# Skema_Gate_Logic.net
KiCad netlist of a schematic drawn in Altium Designer
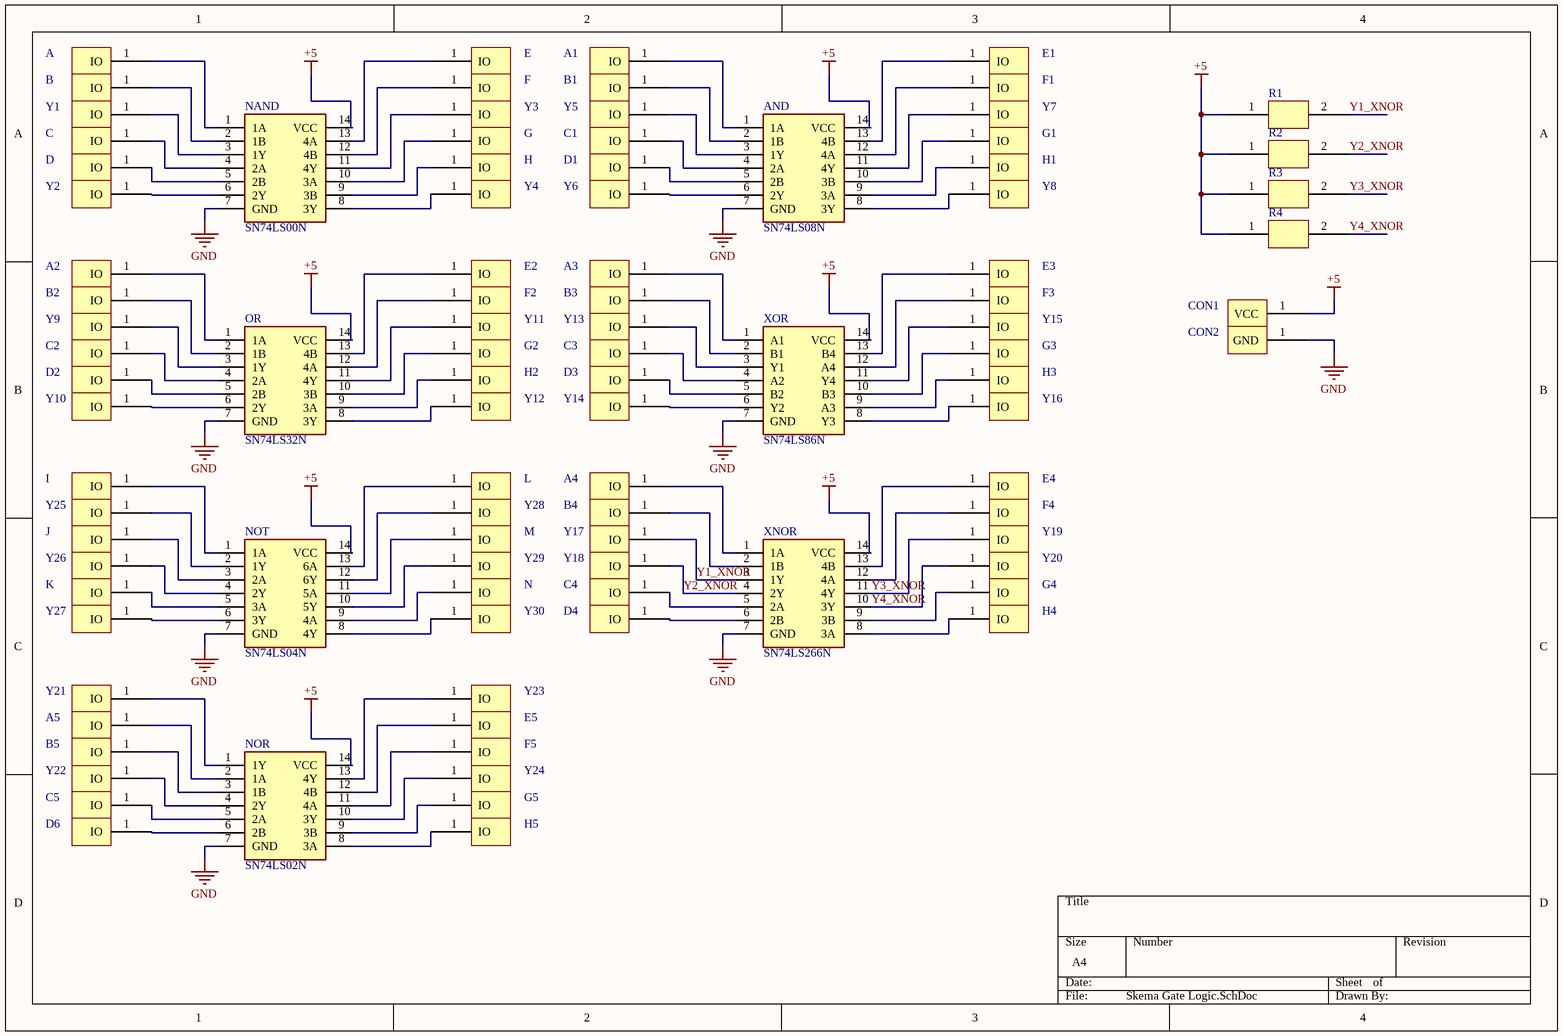
[diagram p0: Skema Gate Logic.SchDoc]

(export (version "E")
  (design (tool "Eeschema 10.0.6"))
  (components
    (comp (ref "A")
      (value "Female_Connector_Banana")
      (footprint "F_Banana")
      (libsource (lib "") (part "Female_Connector_Banana_1"))
    )
    (comp (ref "A1")
      (value "Female_Connector_Banana")
      (footprint "F_Banana")
      (libsource (lib "") (part "Female_Connector_Banana_1"))
    )
    (comp (ref "A2")
      (value "Female_Connector_Banana")
      (footprint "F_Banana")
      (libsource (lib "") (part "Female_Connector_Banana_1"))
    )
    (comp (ref "A3")
      (value "Female_Connector_Banana")
      (footprint "F_Banana")
      (libsource (lib "") (part "Female_Connector_Banana_1"))
    )
    (comp (ref "A4")
      (value "Female_Connector_Banana")
      (footprint "F_Banana")
      (libsource (lib "") (part "Female_Connector_Banana_1"))
    )
    (comp (ref "A5")
      (value "Female_Connector_Banana")
      (footprint "F_Banana")
      (libsource (lib "") (part "Female_Connector_Banana_1"))
    )
    (comp (ref "AND")
      (value "SN74LS08N")
      (footprint "SamacSys:DIP794W53P254L1930H508Q14N")
      (description "Integrated Circuit")
      (fields (field (name "MOUSER PART NUMBER") "595-SN74LS08N"))
      (libsource (lib "SamacSys") (part "SN74LS08N"))
    )
    (comp (ref "B")
      (value "Female_Connector_Banana")
      (footprint "F_Banana")
      (libsource (lib "") (part "Female_Connector_Banana_1"))
    )
    (comp (ref "B1")
      (value "Female_Connector_Banana")
      (footprint "F_Banana")
      (libsource (lib "") (part "Female_Connector_Banana_1"))
    )
    (comp (ref "B2")
      (value "Female_Connector_Banana")
      (footprint "F_Banana")
      (libsource (lib "") (part "Female_Connector_Banana_1"))
    )
    (comp (ref "B3")
      (value "Female_Connector_Banana")
      (footprint "F_Banana")
      (libsource (lib "") (part "Female_Connector_Banana_1"))
    )
    (comp (ref "B4")
      (value "Female_Connector_Banana")
      (footprint "F_Banana")
      (libsource (lib "") (part "Female_Connector_Banana_1"))
    )
    (comp (ref "B5")
      (value "Female_Connector_Banana")
      (footprint "F_Banana")
      (libsource (lib "") (part "Female_Connector_Banana_1"))
    )
    (comp (ref "C")
      (value "Female_Connector_Banana")
      (footprint "F_Banana")
      (libsource (lib "") (part "Female_Connector_Banana_1"))
    )
    (comp (ref "C1")
      (value "Female_Connector_Banana")
      (footprint "F_Banana")
      (libsource (lib "") (part "Female_Connector_Banana_1"))
    )
    (comp (ref "C2")
      (value "Female_Connector_Banana")
      (footprint "F_Banana")
      (libsource (lib "") (part "Female_Connector_Banana_1"))
    )
    (comp (ref "C3")
      (value "Female_Connector_Banana")
      (footprint "F_Banana")
      (libsource (lib "") (part "Female_Connector_Banana_1"))
    )
    (comp (ref "C4")
      (value "Female_Connector_Banana")
      (footprint "F_Banana")
      (libsource (lib "") (part "Female_Connector_Banana_1"))
    )
    (comp (ref "C5")
      (value "Female_Connector_Banana")
      (footprint "F_Banana")
      (libsource (lib "") (part "Female_Connector_Banana_1"))
    )
    (comp (ref "CON1")
      (value "Female_Connector_Banana")
      (footprint "F_Banana")
      (libsource (lib "") (part "Female_Connector_Banana_3"))
    )
    (comp (ref "CON2")
      (value "Female_Connector_Banana")
      (footprint "F_Banana")
      (libsource (lib "") (part "Female_Connector_Banana_2"))
    )
    (comp (ref "D")
      (value "Female_Connector_Banana")
      (footprint "F_Banana")
      (libsource (lib "") (part "Female_Connector_Banana_1"))
    )
    (comp (ref "D1")
      (value "Female_Connector_Banana")
      (footprint "F_Banana")
      (libsource (lib "") (part "Female_Connector_Banana_1"))
    )
    (comp (ref "D2")
      (value "Female_Connector_Banana")
      (footprint "F_Banana")
      (libsource (lib "") (part "Female_Connector_Banana_1"))
    )
    (comp (ref "D3")
      (value "Female_Connector_Banana")
      (footprint "F_Banana")
      (libsource (lib "") (part "Female_Connector_Banana_1"))
    )
    (comp (ref "D4")
      (value "Female_Connector_Banana")
      (footprint "F_Banana")
      (libsource (lib "") (part "Female_Connector_Banana_1"))
    )
    (comp (ref "D6")
      (value "Female_Connector_Banana")
      (footprint "F_Banana")
      (libsource (lib "") (part "Female_Connector_Banana_1"))
    )
    (comp (ref "E")
      (value "Female_Connector_Banana")
      (footprint "F_Banana")
      (libsource (lib "SamacSys") (part "Female_Connector_Banana"))
    )
    (comp (ref "E1")
      (value "Female_Connector_Banana")
      (footprint "F_Banana")
      (libsource (lib "SamacSys") (part "Female_Connector_Banana"))
    )
    (comp (ref "E2")
      (value "Female_Connector_Banana")
      (footprint "F_Banana")
      (libsource (lib "SamacSys") (part "Female_Connector_Banana"))
    )
    (comp (ref "E3")
      (value "Female_Connector_Banana")
      (footprint "F_Banana")
      (libsource (lib "SamacSys") (part "Female_Connector_Banana"))
    )
    (comp (ref "E4")
      (value "Female_Connector_Banana")
      (footprint "F_Banana")
      (libsource (lib "SamacSys") (part "Female_Connector_Banana"))
    )
    (comp (ref "E5")
      (value "Female_Connector_Banana")
      (footprint "F_Banana")
      (libsource (lib "SamacSys") (part "Female_Connector_Banana"))
    )
    (comp (ref "F")
      (value "Female_Connector_Banana")
      (footprint "F_Banana")
      (libsource (lib "SamacSys") (part "Female_Connector_Banana"))
    )
    (comp (ref "F1")
      (value "Female_Connector_Banana")
      (footprint "F_Banana")
      (libsource (lib "SamacSys") (part "Female_Connector_Banana"))
    )
    (comp (ref "F2")
      (value "Female_Connector_Banana")
      (footprint "F_Banana")
      (libsource (lib "SamacSys") (part "Female_Connector_Banana"))
    )
    (comp (ref "F3")
      (value "Female_Connector_Banana")
      (footprint "F_Banana")
      (libsource (lib "SamacSys") (part "Female_Connector_Banana"))
    )
    (comp (ref "F4")
      (value "Female_Connector_Banana")
      (footprint "F_Banana")
      (libsource (lib "SamacSys") (part "Female_Connector_Banana"))
    )
    (comp (ref "F5")
      (value "Female_Connector_Banana")
      (footprint "F_Banana")
      (libsource (lib "SamacSys") (part "Female_Connector_Banana"))
    )
    (comp (ref "G")
      (value "Female_Connector_Banana")
      (footprint "F_Banana")
      (libsource (lib "SamacSys") (part "Female_Connector_Banana"))
    )
    (comp (ref "G1")
      (value "Female_Connector_Banana")
      (footprint "F_Banana")
      (libsource (lib "SamacSys") (part "Female_Connector_Banana"))
    )
    (comp (ref "G2")
      (value "Female_Connector_Banana")
      (footprint "F_Banana")
      (libsource (lib "SamacSys") (part "Female_Connector_Banana"))
    )
    (comp (ref "G3")
      (value "Female_Connector_Banana")
      (footprint "F_Banana")
      (libsource (lib "SamacSys") (part "Female_Connector_Banana"))
    )
    (comp (ref "G4")
      (value "Female_Connector_Banana")
      (footprint "F_Banana")
      (libsource (lib "SamacSys") (part "Female_Connector_Banana"))
    )
    (comp (ref "G5")
      (value "Female_Connector_Banana")
      (footprint "F_Banana")
      (libsource (lib "SamacSys") (part "Female_Connector_Banana"))
    )
    (comp (ref "H")
      (value "Female_Connector_Banana")
      (footprint "F_Banana")
      (libsource (lib "SamacSys") (part "Female_Connector_Banana"))
    )
    (comp (ref "H1")
      (value "Female_Connector_Banana")
      (footprint "F_Banana")
      (libsource (lib "SamacSys") (part "Female_Connector_Banana"))
    )
    (comp (ref "H2")
      (value "Female_Connector_Banana")
      (footprint "F_Banana")
      (libsource (lib "SamacSys") (part "Female_Connector_Banana"))
    )
    (comp (ref "H3")
      (value "Female_Connector_Banana")
      (footprint "F_Banana")
      (libsource (lib "SamacSys") (part "Female_Connector_Banana"))
    )
    (comp (ref "H4")
      (value "Female_Connector_Banana")
      (footprint "F_Banana")
      (libsource (lib "SamacSys") (part "Female_Connector_Banana"))
    )
    (comp (ref "H5")
      (value "Female_Connector_Banana")
      (footprint "F_Banana")
      (libsource (lib "SamacSys") (part "Female_Connector_Banana"))
    )
    (comp (ref "I")
      (value "Female_Connector_Banana")
      (footprint "F_Banana")
      (libsource (lib "") (part "Female_Connector_Banana_1"))
    )
    (comp (ref "J")
      (value "Female_Connector_Banana")
      (footprint "F_Banana")
      (libsource (lib "") (part "Female_Connector_Banana_1"))
    )
    (comp (ref "K")
      (value "Female_Connector_Banana")
      (footprint "F_Banana")
      (libsource (lib "") (part "Female_Connector_Banana_1"))
    )
    (comp (ref "L")
      (value "Female_Connector_Banana")
      (footprint "F_Banana")
      (libsource (lib "SamacSys") (part "Female_Connector_Banana"))
    )
    (comp (ref "M")
      (value "Female_Connector_Banana")
      (footprint "F_Banana")
      (libsource (lib "SamacSys") (part "Female_Connector_Banana"))
    )
    (comp (ref "N")
      (value "Female_Connector_Banana")
      (footprint "F_Banana")
      (libsource (lib "SamacSys") (part "Female_Connector_Banana"))
    )
    (comp (ref "NAND")
      (value "SN74LS00N")
      (footprint "SamacSys:DIP794W53P254L1930H508Q14N")
      (description "Integrated Circuit")
      (fields (field (name "MOUSER PART NUMBER") "595-SN74LS00N"))
      (libsource (lib "SamacSys") (part "SN74LS00N"))
    )
    (comp (ref "NOR")
      (value "SN74LS02N")
      (footprint "SamacSys:DIP794W53P254L1930H508Q14N")
      (description "Integrated Circuit")
      (fields (field (name "MOUSER PART NUMBER") "595-SN74LS02N"))
      (libsource (lib "SamacSys") (part "SN74LS02N"))
    )
    (comp (ref "NOT")
      (value "SN74LS04N")
      (footprint "SamacSys:DIP794W53P254L1930H508Q14N")
      (description "Integrated Circuit")
      (fields (field (name "MOUSER PART NUMBER") "595-SN74LS04N"))
      (libsource (lib "SamacSys") (part "SN74LS04N"))
    )
    (comp (ref "OR")
      (value "SN74LS32N")
      (footprint "SamacSys:DIP794W53P254L1930H508Q14N")
      (description "Integrated Circuit")
      (fields (field (name "MOUSER PART NUMBER") "595-SN74LS32N"))
      (libsource (lib "SamacSys") (part "SN74LS32N"))
    )
    (comp (ref "R1")
      (value "Resistor")
      (footprint "Resistor")
      (description "Fixed Resistance")
      (libsource (lib "Header") (part "Resistor"))
    )
    (comp (ref "R2")
      (value "Resistor")
      (footprint "Resistor")
      (description "Fixed Resistance")
      (libsource (lib "Header") (part "Resistor"))
    )
    (comp (ref "R3")
      (value "Resistor")
      (footprint "Resistor")
      (description "Fixed Resistance")
      (libsource (lib "Header") (part "Resistor"))
    )
    (comp (ref "R4")
      (value "Resistor")
      (footprint "Resistor")
      (description "Fixed Resistance")
      (libsource (lib "Header") (part "Resistor"))
    )
    (comp (ref "XNOR")
      (value "SN74LS266N")
      (footprint "SamacSys:DIP794W53P254L1930H508Q14N")
      (description "Integrated Circuit")
      (fields (field (name "MOUSER PART NUMBER") "595-SN74LS266N"))
      (libsource (lib "SamacSys") (part "SN74LS266N"))
    )
    (comp (ref "XOR")
      (value "SN74LS86N")
      (footprint "SamacSys:DIP794W53P254L1930H508Q14N")
      (description "Integrated Circuit")
      (libsource (lib "SamacSys") (part "SN74LS86N"))
    )
    (comp (ref "Y1")
      (value "Female_Connector_Banana")
      (footprint "F_Banana")
      (libsource (lib "") (part "Female_Connector_Banana_1"))
    )
    (comp (ref "Y2")
      (value "Female_Connector_Banana")
      (footprint "F_Banana")
      (libsource (lib "") (part "Female_Connector_Banana_1"))
    )
    (comp (ref "Y3")
      (value "Female_Connector_Banana")
      (footprint "F_Banana")
      (libsource (lib "SamacSys") (part "Female_Connector_Banana"))
    )
    (comp (ref "Y4")
      (value "Female_Connector_Banana")
      (footprint "F_Banana")
      (libsource (lib "SamacSys") (part "Female_Connector_Banana"))
    )
    (comp (ref "Y5")
      (value "Female_Connector_Banana")
      (footprint "F_Banana")
      (libsource (lib "") (part "Female_Connector_Banana_1"))
    )
    (comp (ref "Y6")
      (value "Female_Connector_Banana")
      (footprint "F_Banana")
      (libsource (lib "") (part "Female_Connector_Banana_1"))
    )
    (comp (ref "Y7")
      (value "Female_Connector_Banana")
      (footprint "F_Banana")
      (libsource (lib "SamacSys") (part "Female_Connector_Banana"))
    )
    (comp (ref "Y8")
      (value "Female_Connector_Banana")
      (footprint "F_Banana")
      (libsource (lib "SamacSys") (part "Female_Connector_Banana"))
    )
    (comp (ref "Y9")
      (value "Female_Connector_Banana")
      (footprint "F_Banana")
      (libsource (lib "") (part "Female_Connector_Banana_1"))
    )
    (comp (ref "Y10")
      (value "Female_Connector_Banana")
      (footprint "F_Banana")
      (libsource (lib "") (part "Female_Connector_Banana_1"))
    )
    (comp (ref "Y11")
      (value "Female_Connector_Banana")
      (footprint "F_Banana")
      (libsource (lib "SamacSys") (part "Female_Connector_Banana"))
    )
    (comp (ref "Y12")
      (value "Female_Connector_Banana")
      (footprint "F_Banana")
      (libsource (lib "SamacSys") (part "Female_Connector_Banana"))
    )
    (comp (ref "Y13")
      (value "Female_Connector_Banana")
      (footprint "F_Banana")
      (libsource (lib "") (part "Female_Connector_Banana_1"))
    )
    (comp (ref "Y14")
      (value "Female_Connector_Banana")
      (footprint "F_Banana")
      (libsource (lib "") (part "Female_Connector_Banana_1"))
    )
    (comp (ref "Y15")
      (value "Female_Connector_Banana")
      (footprint "F_Banana")
      (libsource (lib "SamacSys") (part "Female_Connector_Banana"))
    )
    (comp (ref "Y16")
      (value "Female_Connector_Banana")
      (footprint "F_Banana")
      (libsource (lib "SamacSys") (part "Female_Connector_Banana"))
    )
    (comp (ref "Y17")
      (value "Female_Connector_Banana")
      (footprint "F_Banana")
      (libsource (lib "") (part "Female_Connector_Banana_1"))
    )
    (comp (ref "Y18")
      (value "Female_Connector_Banana")
      (footprint "F_Banana")
      (libsource (lib "") (part "Female_Connector_Banana_1"))
    )
    (comp (ref "Y19")
      (value "Female_Connector_Banana")
      (footprint "F_Banana")
      (libsource (lib "SamacSys") (part "Female_Connector_Banana"))
    )
    (comp (ref "Y20")
      (value "Female_Connector_Banana")
      (footprint "F_Banana")
      (libsource (lib "SamacSys") (part "Female_Connector_Banana"))
    )
    (comp (ref "Y21")
      (value "Female_Connector_Banana")
      (footprint "F_Banana")
      (libsource (lib "") (part "Female_Connector_Banana_1"))
    )
    (comp (ref "Y22")
      (value "Female_Connector_Banana")
      (footprint "F_Banana")
      (libsource (lib "") (part "Female_Connector_Banana_1"))
    )
    (comp (ref "Y23")
      (value "Female_Connector_Banana")
      (footprint "F_Banana")
      (libsource (lib "SamacSys") (part "Female_Connector_Banana"))
    )
    (comp (ref "Y24")
      (value "Female_Connector_Banana")
      (footprint "F_Banana")
      (libsource (lib "SamacSys") (part "Female_Connector_Banana"))
    )
    (comp (ref "Y25")
      (value "Female_Connector_Banana")
      (footprint "F_Banana")
      (libsource (lib "") (part "Female_Connector_Banana_1"))
    )
    (comp (ref "Y26")
      (value "Female_Connector_Banana")
      (footprint "F_Banana")
      (libsource (lib "") (part "Female_Connector_Banana_1"))
    )
    (comp (ref "Y27")
      (value "Female_Connector_Banana")
      (footprint "F_Banana")
      (libsource (lib "") (part "Female_Connector_Banana_1"))
    )
    (comp (ref "Y28")
      (value "Female_Connector_Banana")
      (footprint "F_Banana")
      (libsource (lib "SamacSys") (part "Female_Connector_Banana"))
    )
    (comp (ref "Y29")
      (value "Female_Connector_Banana")
      (footprint "F_Banana")
      (libsource (lib "SamacSys") (part "Female_Connector_Banana"))
    )
    (comp (ref "Y30")
      (value "Female_Connector_Banana")
      (footprint "F_Banana")
      (libsource (lib "SamacSys") (part "Female_Connector_Banana"))
    )
  )
  (nets
    (net (code "1") (name "+5") (class "Default")
      (node (ref "AND") (pin "14") (pinfunction "VCC_14") (pintype "passive"))
      (node (ref "CON1") (pin "1") (pinfunction "VCC_1") (pintype "passive"))
      (node (ref "NAND") (pin "14") (pinfunction "VCC_14") (pintype "passive"))
      (node (ref "NOR") (pin "14") (pinfunction "VCC_14") (pintype "passive"))
      (node (ref "NOT") (pin "14") (pinfunction "VCC_14") (pintype "passive"))
      (node (ref "OR") (pin "14") (pinfunction "VCC_14") (pintype "passive"))
      (node (ref "R1") (pin "1") (pinfunction "1_1") (pintype "passive"))
      (node (ref "R2") (pin "1") (pinfunction "1_1") (pintype "passive"))
      (node (ref "R3") (pin "1") (pinfunction "1_1") (pintype "passive"))
      (node (ref "R4") (pin "1") (pinfunction "1_1") (pintype "passive"))
      (node (ref "XNOR") (pin "14") (pinfunction "VCC_14") (pintype "passive"))
      (node (ref "XOR") (pin "14") (pinfunction "VCC_14") (pintype "passive"))
    )
    (net (code "2") (name "/Y1_XNOR") (class "Default")
      (node (ref "R1") (pin "2") (pinfunction "2_2") (pintype "passive"))
      (node (ref "XNOR") (pin "3") (pinfunction "1Y_3") (pintype "passive"))
      (node (ref "Y17") (pin "1") (pinfunction "IO_1") (pintype "passive"))
    )
    (net (code "3") (name "/Y2_XNOR") (class "Default")
      (node (ref "R2") (pin "2") (pinfunction "2_2") (pintype "passive"))
      (node (ref "XNOR") (pin "4") (pinfunction "2Y_4") (pintype "passive"))
      (node (ref "Y18") (pin "1") (pinfunction "IO_1") (pintype "passive"))
    )
    (net (code "4") (name "/Y3_XNOR") (class "Default")
      (node (ref "R3") (pin "2") (pinfunction "2_2") (pintype "passive"))
      (node (ref "XNOR") (pin "11") (pinfunction "4Y_11") (pintype "passive"))
      (node (ref "Y19") (pin "1") (pinfunction "IO_1") (pintype "passive"))
    )
    (net (code "5") (name "/Y4_XNOR") (class "Default")
      (node (ref "R4") (pin "2") (pinfunction "2_2") (pintype "passive"))
      (node (ref "XNOR") (pin "10") (pinfunction "3Y_10") (pintype "passive"))
      (node (ref "Y20") (pin "1") (pinfunction "IO_1") (pintype "passive"))
    )
    (net (code "6") (name "GND") (class "Default")
      (node (ref "AND") (pin "7") (pinfunction "GND_7") (pintype "passive"))
      (node (ref "CON2") (pin "1") (pinfunction "GND_1") (pintype "passive"))
      (node (ref "NAND") (pin "7") (pinfunction "GND_7") (pintype "passive"))
      (node (ref "NOR") (pin "7") (pinfunction "GND_7") (pintype "passive"))
      (node (ref "NOT") (pin "7") (pinfunction "GND_7") (pintype "passive"))
      (node (ref "OR") (pin "7") (pinfunction "GND_7") (pintype "passive"))
      (node (ref "XNOR") (pin "7") (pinfunction "GND_7") (pintype "passive"))
      (node (ref "XOR") (pin "7") (pinfunction "GND_7") (pintype "passive"))
    )
    (net (code "7") (name "Net-(A-IO)") (class "Default")
      (node (ref "A") (pin "1") (pinfunction "IO_1") (pintype "passive"))
      (node (ref "NAND") (pin "1") (pinfunction "1A_1") (pintype "passive"))
    )
    (net (code "8") (name "Net-(A1-IO)") (class "Default")
      (node (ref "A1") (pin "1") (pinfunction "IO_1") (pintype "passive"))
      (node (ref "AND") (pin "1") (pinfunction "1A_1") (pintype "passive"))
    )
    (net (code "9") (name "Net-(A2-IO)") (class "Default")
      (node (ref "A2") (pin "1") (pinfunction "IO_1") (pintype "passive"))
      (node (ref "OR") (pin "1") (pinfunction "1A_1") (pintype "passive"))
    )
    (net (code "10") (name "Net-(A3-IO)") (class "Default")
      (node (ref "A3") (pin "1") (pinfunction "IO_1") (pintype "passive"))
      (node (ref "XOR") (pin "1") (pinfunction "A1_1") (pintype "passive"))
    )
    (net (code "11") (name "Net-(A4-IO)") (class "Default")
      (node (ref "A4") (pin "1") (pinfunction "IO_1") (pintype "passive"))
      (node (ref "XNOR") (pin "1") (pinfunction "1A_1") (pintype "passive"))
    )
    (net (code "12") (name "Net-(A5-IO)") (class "Default")
      (node (ref "A5") (pin "1") (pinfunction "IO_1") (pintype "passive"))
      (node (ref "NOR") (pin "2") (pinfunction "1A_2") (pintype "passive"))
    )
    (net (code "13") (name "Net-(AND-1B)") (class "Default")
      (node (ref "AND") (pin "2") (pinfunction "1B_2") (pintype "passive"))
      (node (ref "B1") (pin "1") (pinfunction "IO_1") (pintype "passive"))
    )
    (net (code "14") (name "Net-(AND-1Y)") (class "Default")
      (node (ref "AND") (pin "3") (pinfunction "1Y_3") (pintype "passive"))
      (node (ref "Y5") (pin "1") (pinfunction "IO_1") (pintype "passive"))
    )
    (net (code "15") (name "Net-(AND-2A)") (class "Default")
      (node (ref "AND") (pin "4") (pinfunction "2A_4") (pintype "passive"))
      (node (ref "C1") (pin "1") (pinfunction "IO_1") (pintype "passive"))
    )
    (net (code "16") (name "Net-(AND-2B)") (class "Default")
      (node (ref "AND") (pin "5") (pinfunction "2B_5") (pintype "passive"))
      (node (ref "D1") (pin "1") (pinfunction "IO_1") (pintype "passive"))
    )
    (net (code "17") (name "Net-(AND-2Y)") (class "Default")
      (node (ref "AND") (pin "6") (pinfunction "2Y_6") (pintype "passive"))
      (node (ref "Y6") (pin "1") (pinfunction "IO_1") (pintype "passive"))
    )
    (net (code "18") (name "Net-(AND-3A)") (class "Default")
      (node (ref "AND") (pin "9") (pinfunction "3A_9") (pintype "passive"))
      (node (ref "H1") (pin "1") (pinfunction "IO_1") (pintype "passive"))
    )
    (net (code "19") (name "Net-(AND-3B)") (class "Default")
      (node (ref "AND") (pin "10") (pinfunction "3B_10") (pintype "passive"))
      (node (ref "G1") (pin "1") (pinfunction "IO_1") (pintype "passive"))
    )
    (net (code "20") (name "Net-(AND-3Y)") (class "Default")
      (node (ref "AND") (pin "8") (pinfunction "3Y_8") (pintype "passive"))
      (node (ref "Y8") (pin "1") (pinfunction "IO_1") (pintype "passive"))
    )
    (net (code "21") (name "Net-(AND-4A)") (class "Default")
      (node (ref "AND") (pin "12") (pinfunction "4A_12") (pintype "passive"))
      (node (ref "F1") (pin "1") (pinfunction "IO_1") (pintype "passive"))
    )
    (net (code "22") (name "Net-(AND-4B)") (class "Default")
      (node (ref "AND") (pin "13") (pinfunction "4B_13") (pintype "passive"))
      (node (ref "E1") (pin "1") (pinfunction "IO_1") (pintype "passive"))
    )
    (net (code "23") (name "Net-(AND-4Y)") (class "Default")
      (node (ref "AND") (pin "11") (pinfunction "4Y_11") (pintype "passive"))
      (node (ref "Y7") (pin "1") (pinfunction "IO_1") (pintype "passive"))
    )
    (net (code "24") (name "Net-(B-IO)") (class "Default")
      (node (ref "B") (pin "1") (pinfunction "IO_1") (pintype "passive"))
      (node (ref "NAND") (pin "2") (pinfunction "1B_2") (pintype "passive"))
    )
    (net (code "25") (name "Net-(B2-IO)") (class "Default")
      (node (ref "B2") (pin "1") (pinfunction "IO_1") (pintype "passive"))
      (node (ref "OR") (pin "2") (pinfunction "1B_2") (pintype "passive"))
    )
    (net (code "26") (name "Net-(B3-IO)") (class "Default")
      (node (ref "B3") (pin "1") (pinfunction "IO_1") (pintype "passive"))
      (node (ref "XOR") (pin "2") (pinfunction "B1_2") (pintype "passive"))
    )
    (net (code "27") (name "Net-(B4-IO)") (class "Default")
      (node (ref "B4") (pin "1") (pinfunction "IO_1") (pintype "passive"))
      (node (ref "XNOR") (pin "2") (pinfunction "1B_2") (pintype "passive"))
    )
    (net (code "28") (name "Net-(B5-IO)") (class "Default")
      (node (ref "B5") (pin "1") (pinfunction "IO_1") (pintype "passive"))
      (node (ref "NOR") (pin "3") (pinfunction "1B_3") (pintype "passive"))
    )
    (net (code "29") (name "Net-(C-IO)") (class "Default")
      (node (ref "C") (pin "1") (pinfunction "IO_1") (pintype "passive"))
      (node (ref "NAND") (pin "4") (pinfunction "2A_4") (pintype "passive"))
    )
    (net (code "30") (name "Net-(C2-IO)") (class "Default")
      (node (ref "C2") (pin "1") (pinfunction "IO_1") (pintype "passive"))
      (node (ref "OR") (pin "4") (pinfunction "2A_4") (pintype "passive"))
    )
    (net (code "31") (name "Net-(C3-IO)") (class "Default")
      (node (ref "C3") (pin "1") (pinfunction "IO_1") (pintype "passive"))
      (node (ref "XOR") (pin "4") (pinfunction "A2_4") (pintype "passive"))
    )
    (net (code "32") (name "Net-(C4-IO)") (class "Default")
      (node (ref "C4") (pin "1") (pinfunction "IO_1") (pintype "passive"))
      (node (ref "XNOR") (pin "5") (pinfunction "2A_5") (pintype "passive"))
    )
    (net (code "33") (name "Net-(C5-IO)") (class "Default")
      (node (ref "C5") (pin "1") (pinfunction "IO_1") (pintype "passive"))
      (node (ref "NOR") (pin "5") (pinfunction "2A_5") (pintype "passive"))
    )
    (net (code "34") (name "Net-(D-IO)") (class "Default")
      (node (ref "D") (pin "1") (pinfunction "IO_1") (pintype "passive"))
      (node (ref "NAND") (pin "5") (pinfunction "2B_5") (pintype "passive"))
    )
    (net (code "35") (name "Net-(D2-IO)") (class "Default")
      (node (ref "D2") (pin "1") (pinfunction "IO_1") (pintype "passive"))
      (node (ref "OR") (pin "5") (pinfunction "2B_5") (pintype "passive"))
    )
    (net (code "36") (name "Net-(D3-IO)") (class "Default")
      (node (ref "D3") (pin "1") (pinfunction "IO_1") (pintype "passive"))
      (node (ref "XOR") (pin "5") (pinfunction "B2_5") (pintype "passive"))
    )
    (net (code "37") (name "Net-(D4-IO)") (class "Default")
      (node (ref "D4") (pin "1") (pinfunction "IO_1") (pintype "passive"))
      (node (ref "XNOR") (pin "6") (pinfunction "2B_6") (pintype "passive"))
    )
    (net (code "38") (name "Net-(D6-IO)") (class "Default")
      (node (ref "D6") (pin "1") (pinfunction "IO_1") (pintype "passive"))
      (node (ref "NOR") (pin "6") (pinfunction "2B_6") (pintype "passive"))
    )
    (net (code "39") (name "Net-(E-IO)") (class "Default")
      (node (ref "E") (pin "1") (pinfunction "IO_1") (pintype "passive"))
      (node (ref "NAND") (pin "13") (pinfunction "4A_13") (pintype "passive"))
    )
    (net (code "40") (name "Net-(E2-IO)") (class "Default")
      (node (ref "E2") (pin "1") (pinfunction "IO_1") (pintype "passive"))
      (node (ref "OR") (pin "13") (pinfunction "4B_13") (pintype "passive"))
    )
    (net (code "41") (name "Net-(E3-IO)") (class "Default")
      (node (ref "E3") (pin "1") (pinfunction "IO_1") (pintype "passive"))
      (node (ref "XOR") (pin "13") (pinfunction "B4_13") (pintype "passive"))
    )
    (net (code "42") (name "Net-(E4-IO)") (class "Default")
      (node (ref "E4") (pin "1") (pinfunction "IO_1") (pintype "passive"))
      (node (ref "XNOR") (pin "13") (pinfunction "4B_13") (pintype "passive"))
    )
    (net (code "43") (name "Net-(E5-IO)") (class "Default")
      (node (ref "E5") (pin "1") (pinfunction "IO_1") (pintype "passive"))
      (node (ref "NOR") (pin "12") (pinfunction "4B_12") (pintype "passive"))
    )
    (net (code "44") (name "Net-(F-IO)") (class "Default")
      (node (ref "F") (pin "1") (pinfunction "IO_1") (pintype "passive"))
      (node (ref "NAND") (pin "12") (pinfunction "4B_12") (pintype "passive"))
    )
    (net (code "45") (name "Net-(F2-IO)") (class "Default")
      (node (ref "F2") (pin "1") (pinfunction "IO_1") (pintype "passive"))
      (node (ref "OR") (pin "12") (pinfunction "4A_12") (pintype "passive"))
    )
    (net (code "46") (name "Net-(F3-IO)") (class "Default")
      (node (ref "F3") (pin "1") (pinfunction "IO_1") (pintype "passive"))
      (node (ref "XOR") (pin "12") (pinfunction "A4_12") (pintype "passive"))
    )
    (net (code "47") (name "Net-(F4-IO)") (class "Default")
      (node (ref "F4") (pin "1") (pinfunction "IO_1") (pintype "passive"))
      (node (ref "XNOR") (pin "12") (pinfunction "4A_12") (pintype "passive"))
    )
    (net (code "48") (name "Net-(F5-IO)") (class "Default")
      (node (ref "F5") (pin "1") (pinfunction "IO_1") (pintype "passive"))
      (node (ref "NOR") (pin "11") (pinfunction "4A_11") (pintype "passive"))
    )
    (net (code "49") (name "Net-(G-IO)") (class "Default")
      (node (ref "G") (pin "1") (pinfunction "IO_1") (pintype "passive"))
      (node (ref "NAND") (pin "10") (pinfunction "3A_10") (pintype "passive"))
    )
    (net (code "50") (name "Net-(G2-IO)") (class "Default")
      (node (ref "G2") (pin "1") (pinfunction "IO_1") (pintype "passive"))
      (node (ref "OR") (pin "10") (pinfunction "3B_10") (pintype "passive"))
    )
    (net (code "51") (name "Net-(G3-IO)") (class "Default")
      (node (ref "G3") (pin "1") (pinfunction "IO_1") (pintype "passive"))
      (node (ref "XOR") (pin "10") (pinfunction "B3_10") (pintype "passive"))
    )
    (net (code "52") (name "Net-(G4-IO)") (class "Default")
      (node (ref "G4") (pin "1") (pinfunction "IO_1") (pintype "passive"))
      (node (ref "XNOR") (pin "9") (pinfunction "3B_9") (pintype "passive"))
    )
    (net (code "53") (name "Net-(G5-IO)") (class "Default")
      (node (ref "G5") (pin "1") (pinfunction "IO_1") (pintype "passive"))
      (node (ref "NOR") (pin "9") (pinfunction "3B_9") (pintype "passive"))
    )
    (net (code "54") (name "Net-(H-IO)") (class "Default")
      (node (ref "H") (pin "1") (pinfunction "IO_1") (pintype "passive"))
      (node (ref "NAND") (pin "9") (pinfunction "3B_9") (pintype "passive"))
    )
    (net (code "55") (name "Net-(H2-IO)") (class "Default")
      (node (ref "H2") (pin "1") (pinfunction "IO_1") (pintype "passive"))
      (node (ref "OR") (pin "9") (pinfunction "3A_9") (pintype "passive"))
    )
    (net (code "56") (name "Net-(H3-IO)") (class "Default")
      (node (ref "H3") (pin "1") (pinfunction "IO_1") (pintype "passive"))
      (node (ref "XOR") (pin "9") (pinfunction "A3_9") (pintype "passive"))
    )
    (net (code "57") (name "Net-(H4-IO)") (class "Default")
      (node (ref "H4") (pin "1") (pinfunction "IO_1") (pintype "passive"))
      (node (ref "XNOR") (pin "8") (pinfunction "3A_8") (pintype "passive"))
    )
    (net (code "58") (name "Net-(H5-IO)") (class "Default")
      (node (ref "H5") (pin "1") (pinfunction "IO_1") (pintype "passive"))
      (node (ref "NOR") (pin "8") (pinfunction "3A_8") (pintype "passive"))
    )
    (net (code "59") (name "Net-(I-IO)") (class "Default")
      (node (ref "I") (pin "1") (pinfunction "IO_1") (pintype "passive"))
      (node (ref "NOT") (pin "1") (pinfunction "1A_1") (pintype "passive"))
    )
    (net (code "60") (name "Net-(J-IO)") (class "Default")
      (node (ref "J") (pin "1") (pinfunction "IO_1") (pintype "passive"))
      (node (ref "NOT") (pin "3") (pinfunction "2A_3") (pintype "passive"))
    )
    (net (code "61") (name "Net-(K-IO)") (class "Default")
      (node (ref "K") (pin "1") (pinfunction "IO_1") (pintype "passive"))
      (node (ref "NOT") (pin "5") (pinfunction "3A_5") (pintype "passive"))
    )
    (net (code "62") (name "Net-(L-IO)") (class "Default")
      (node (ref "L") (pin "1") (pinfunction "IO_1") (pintype "passive"))
      (node (ref "NOT") (pin "13") (pinfunction "6A_13") (pintype "passive"))
    )
    (net (code "63") (name "Net-(M-IO)") (class "Default")
      (node (ref "M") (pin "1") (pinfunction "IO_1") (pintype "passive"))
      (node (ref "NOT") (pin "11") (pinfunction "5A_11") (pintype "passive"))
    )
    (net (code "64") (name "Net-(N-IO)") (class "Default")
      (node (ref "N") (pin "1") (pinfunction "IO_1") (pintype "passive"))
      (node (ref "NOT") (pin "9") (pinfunction "4A_9") (pintype "passive"))
    )
    (net (code "65") (name "Net-(NAND-1Y)") (class "Default")
      (node (ref "NAND") (pin "3") (pinfunction "1Y_3") (pintype "passive"))
      (node (ref "Y1") (pin "1") (pinfunction "IO_1") (pintype "passive"))
    )
    (net (code "66") (name "Net-(NAND-2Y)") (class "Default")
      (node (ref "NAND") (pin "6") (pinfunction "2Y_6") (pintype "passive"))
      (node (ref "Y2") (pin "1") (pinfunction "IO_1") (pintype "passive"))
    )
    (net (code "67") (name "Net-(NAND-3Y)") (class "Default")
      (node (ref "NAND") (pin "8") (pinfunction "3Y_8") (pintype "passive"))
      (node (ref "Y4") (pin "1") (pinfunction "IO_1") (pintype "passive"))
    )
    (net (code "68") (name "Net-(NAND-4Y)") (class "Default")
      (node (ref "NAND") (pin "11") (pinfunction "4Y_11") (pintype "passive"))
      (node (ref "Y3") (pin "1") (pinfunction "IO_1") (pintype "passive"))
    )
    (net (code "69") (name "Net-(NOR-1Y)") (class "Default")
      (node (ref "NOR") (pin "1") (pinfunction "1Y_1") (pintype "passive"))
      (node (ref "Y21") (pin "1") (pinfunction "IO_1") (pintype "passive"))
    )
    (net (code "70") (name "Net-(NOR-2Y)") (class "Default")
      (node (ref "NOR") (pin "4") (pinfunction "2Y_4") (pintype "passive"))
      (node (ref "Y22") (pin "1") (pinfunction "IO_1") (pintype "passive"))
    )
    (net (code "71") (name "Net-(NOR-3Y)") (class "Default")
      (node (ref "NOR") (pin "10") (pinfunction "3Y_10") (pintype "passive"))
      (node (ref "Y24") (pin "1") (pinfunction "IO_1") (pintype "passive"))
    )
    (net (code "72") (name "Net-(NOR-4Y)") (class "Default")
      (node (ref "NOR") (pin "13") (pinfunction "4Y_13") (pintype "passive"))
      (node (ref "Y23") (pin "1") (pinfunction "IO_1") (pintype "passive"))
    )
    (net (code "73") (name "Net-(NOT-1Y)") (class "Default")
      (node (ref "NOT") (pin "2") (pinfunction "1Y_2") (pintype "passive"))
      (node (ref "Y25") (pin "1") (pinfunction "IO_1") (pintype "passive"))
    )
    (net (code "74") (name "Net-(NOT-2Y)") (class "Default")
      (node (ref "NOT") (pin "4") (pinfunction "2Y_4") (pintype "passive"))
      (node (ref "Y26") (pin "1") (pinfunction "IO_1") (pintype "passive"))
    )
    (net (code "75") (name "Net-(NOT-3Y)") (class "Default")
      (node (ref "NOT") (pin "6") (pinfunction "3Y_6") (pintype "passive"))
      (node (ref "Y27") (pin "1") (pinfunction "IO_1") (pintype "passive"))
    )
    (net (code "76") (name "Net-(NOT-4Y)") (class "Default")
      (node (ref "NOT") (pin "8") (pinfunction "4Y_8") (pintype "passive"))
      (node (ref "Y30") (pin "1") (pinfunction "IO_1") (pintype "passive"))
    )
    (net (code "77") (name "Net-(NOT-5Y)") (class "Default")
      (node (ref "NOT") (pin "10") (pinfunction "5Y_10") (pintype "passive"))
      (node (ref "Y29") (pin "1") (pinfunction "IO_1") (pintype "passive"))
    )
    (net (code "78") (name "Net-(NOT-6Y)") (class "Default")
      (node (ref "NOT") (pin "12") (pinfunction "6Y_12") (pintype "passive"))
      (node (ref "Y28") (pin "1") (pinfunction "IO_1") (pintype "passive"))
    )
    (net (code "79") (name "Net-(OR-1Y)") (class "Default")
      (node (ref "OR") (pin "3") (pinfunction "1Y_3") (pintype "passive"))
      (node (ref "Y9") (pin "1") (pinfunction "IO_1") (pintype "passive"))
    )
    (net (code "80") (name "Net-(OR-2Y)") (class "Default")
      (node (ref "OR") (pin "6") (pinfunction "2Y_6") (pintype "passive"))
      (node (ref "Y10") (pin "1") (pinfunction "IO_1") (pintype "passive"))
    )
    (net (code "81") (name "Net-(OR-3Y)") (class "Default")
      (node (ref "OR") (pin "8") (pinfunction "3Y_8") (pintype "passive"))
      (node (ref "Y12") (pin "1") (pinfunction "IO_1") (pintype "passive"))
    )
    (net (code "82") (name "Net-(OR-4Y)") (class "Default")
      (node (ref "OR") (pin "11") (pinfunction "4Y_11") (pintype "passive"))
      (node (ref "Y11") (pin "1") (pinfunction "IO_1") (pintype "passive"))
    )
    (net (code "83") (name "Net-(XOR-Y1)") (class "Default")
      (node (ref "XOR") (pin "3") (pinfunction "Y1_3") (pintype "passive"))
      (node (ref "Y13") (pin "1") (pinfunction "IO_1") (pintype "passive"))
    )
    (net (code "84") (name "Net-(XOR-Y2)") (class "Default")
      (node (ref "XOR") (pin "6") (pinfunction "Y2_6") (pintype "passive"))
      (node (ref "Y14") (pin "1") (pinfunction "IO_1") (pintype "passive"))
    )
    (net (code "85") (name "Net-(XOR-Y3)") (class "Default")
      (node (ref "XOR") (pin "8") (pinfunction "Y3_8") (pintype "passive"))
      (node (ref "Y16") (pin "1") (pinfunction "IO_1") (pintype "passive"))
    )
    (net (code "86") (name "Net-(XOR-Y4)") (class "Default")
      (node (ref "XOR") (pin "11") (pinfunction "Y4_11") (pintype "passive"))
      (node (ref "Y15") (pin "1") (pinfunction "IO_1") (pintype "passive"))
    )
  )
)
